# Smarttree_BMS_3_2.net
KiCad netlist of a schematic drawn in EAGLE
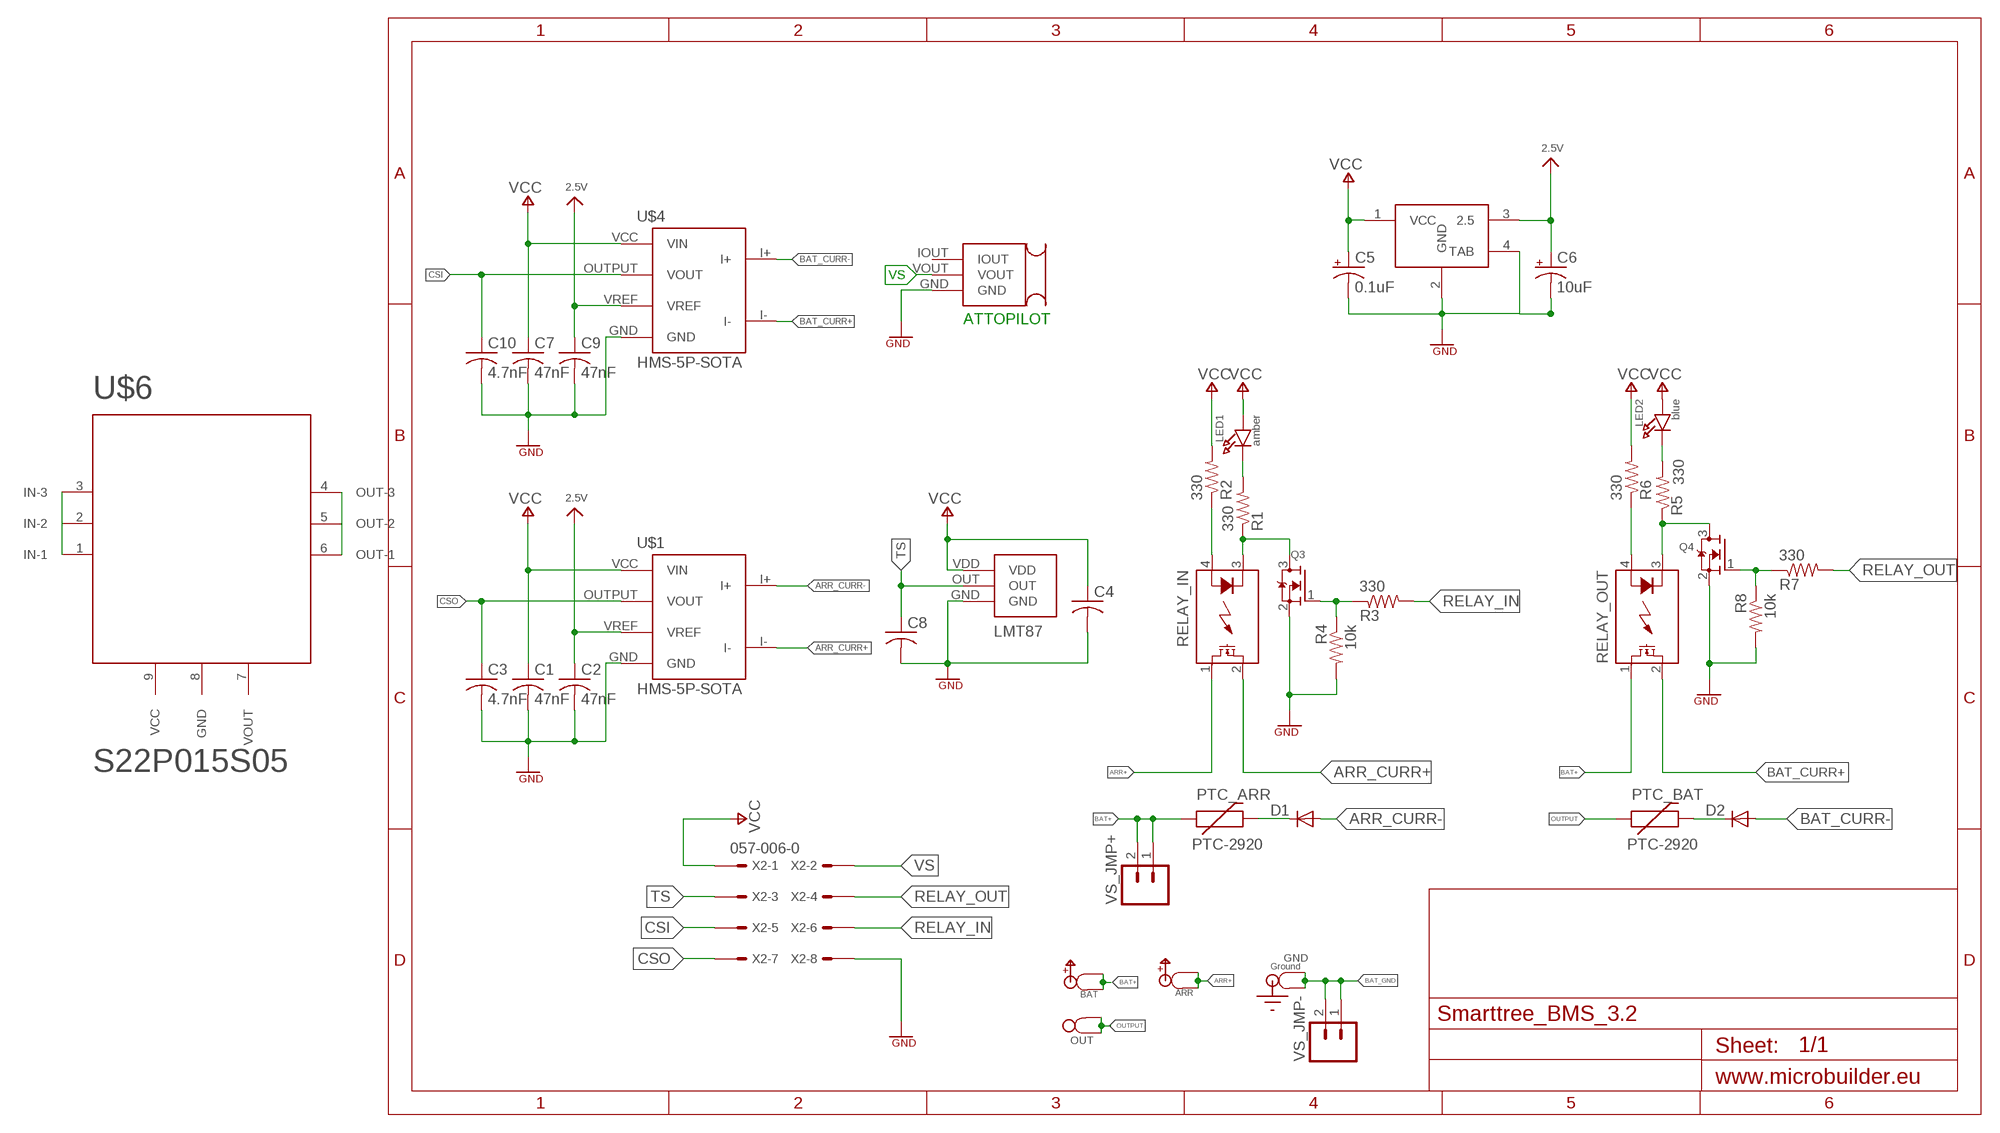
[diagram p0: schematic, sheet 1]

(export (version "E")
  (design (tool "Eeschema 10.0.6"))
  (components
    (comp (ref "ARR")
      (value "SPADE-POWER")
      (footprint "eagle-import:SPADE-POWER")
      (libsource (lib "eagle-import") (part "SPADE-POWER"))
    )
    (comp (ref "ATTOPILOT")
      (value "ATTOPILOT_VOLT")
      (footprint "eagle-import:TH_BKOT")
      (libsource (lib "eagle-import") (part "ATTOPILOT_VOLT"))
    )
    (comp (ref "BAT")
      (value "SPADE-POWER")
      (footprint "eagle-import:SPADE-POWER")
      (libsource (lib "eagle-import") (part "SPADE-POWER"))
    )
    (comp (ref "C1")
      (value "47nF")
      (footprint "eagle-import:C0805")
      (libsource (lib "eagle-import") (part "C-USC0805"))
    )
    (comp (ref "C2")
      (value "47nF")
      (footprint "eagle-import:C0805")
      (libsource (lib "eagle-import") (part "C-USC0805"))
    )
    (comp (ref "C3")
      (value "4.7nF")
      (footprint "eagle-import:C0805")
      (libsource (lib "eagle-import") (part "C-USC0805"))
    )
    (comp (ref "C4")
      (value "C-USC0805")
      (footprint "eagle-import:C0805")
      (libsource (lib "eagle-import") (part "C-USC0805"))
    )
    (comp (ref "C5")
      (value "0.1uF")
      (footprint "eagle-import:EIA3216")
      (libsource (lib "eagle-import") (part "10UF-TANT"))
    )
    (comp (ref "C6")
      (value "10uF")
      (footprint "eagle-import:EIA3216")
      (libsource (lib "eagle-import") (part "10UF-TANT"))
    )
    (comp (ref "C7")
      (value "47nF")
      (footprint "eagle-import:C0805")
      (libsource (lib "eagle-import") (part "C-USC0805"))
    )
    (comp (ref "C8")
      (value "C-USC0805")
      (footprint "eagle-import:C0805")
      (libsource (lib "eagle-import") (part "C-USC0805"))
    )
    (comp (ref "C9")
      (value "47nF")
      (footprint "eagle-import:C0805")
      (libsource (lib "eagle-import") (part "C-USC0805"))
    )
    (comp (ref "C10")
      (value "4.7nF")
      (footprint "eagle-import:C0805")
      (libsource (lib "eagle-import") (part "C-USC0805"))
    )
    (comp (ref "D1")
      (value "DIODE-SOD106-R")
      (footprint "eagle-import:SOD106-R")
      (libsource (lib "eagle-import") (part "DIODE-SOD106-R"))
    )
    (comp (ref "D2")
      (value "DIODE-SOD106-R")
      (footprint "eagle-import:SOD106-R")
      (libsource (lib "eagle-import") (part "DIODE-SOD106-R"))
    )
    (comp (ref "GND")
      (value "SPADE-GROUND")
      (footprint "eagle-import:SPADE-GROUND")
      (libsource (lib "eagle-import") (part "SPADE-GROUND"))
    )
    (comp (ref "LED1")
      (value "amber")
      (footprint "eagle-import:CHIPLED_0805")
      (libsource (lib "eagle-import") (part "LED0805"))
    )
    (comp (ref "LED2")
      (value "blue")
      (footprint "eagle-import:CHIPLED_0805")
      (libsource (lib "eagle-import") (part "LED0805"))
    )
    (comp (ref "LM1117")
      (value "LM2937_SOT223")
      (footprint "eagle-import:SOT223")
      (libsource (lib "eagle-import") (part "LM2937_SOT223"))
    )
    (comp (ref "LMT87")
      (value "LMT87_PAC")
      (footprint "eagle-import:LMT87_TO")
      (libsource (lib "eagle-import") (part "LMT87_PAC"))
    )
    (comp (ref "OUT")
      (value "SPADE-TERMINALPTH")
      (footprint "eagle-import:SPADE-TERMINAL")
      (libsource (lib "eagle-import") (part "SPADE-TERMINALPTH"))
    )
    (comp (ref "PTC_ARR")
      (value "PTC-2920")
      (footprint "eagle-import:PTC-2920")
      (libsource (lib "eagle-import") (part "PTC-2920"))
    )
    (comp (ref "PTC_BAT")
      (value "PTC-2920")
      (footprint "eagle-import:PTC-2920")
      (libsource (lib "eagle-import") (part "PTC-2920"))
    )
    (comp (ref "Q3")
      (value "MOSFET-NREFLOW")
      (footprint "eagle-import:SOT23")
      (libsource (lib "eagle-import") (part "MOSFET-NREFLOW"))
    )
    (comp (ref "Q4")
      (value "MOSFET-NREFLOW")
      (footprint "eagle-import:SOT23")
      (libsource (lib "eagle-import") (part "MOSFET-NREFLOW"))
    )
    (comp (ref "R1")
      (value "330")
      (footprint "eagle-import:R0805")
      (libsource (lib "eagle-import") (part "R-US_R0805"))
    )
    (comp (ref "R2")
      (value "330")
      (footprint "eagle-import:R0805")
      (libsource (lib "eagle-import") (part "R-US_R0805"))
    )
    (comp (ref "R3")
      (value "330")
      (footprint "eagle-import:R0805")
      (libsource (lib "eagle-import") (part "R-US_R0805"))
    )
    (comp (ref "R4")
      (value "10k")
      (footprint "eagle-import:R0805")
      (libsource (lib "eagle-import") (part "R-US_R0805"))
    )
    (comp (ref "R5")
      (value "330")
      (footprint "eagle-import:R0805")
      (libsource (lib "eagle-import") (part "R-US_R0805"))
    )
    (comp (ref "R6")
      (value "330")
      (footprint "eagle-import:R0805")
      (libsource (lib "eagle-import") (part "R-US_R0805"))
    )
    (comp (ref "R7")
      (value "330")
      (footprint "eagle-import:R0805")
      (libsource (lib "eagle-import") (part "R-US_R0805"))
    )
    (comp (ref "R8")
      (value "10k")
      (footprint "eagle-import:R0805")
      (libsource (lib "eagle-import") (part "R-US_R0805"))
    )
    (comp (ref "RELAY_IN")
      (value "CPC1708J")
      (footprint "eagle-import:I4-PAC")
      (libsource (lib "eagle-import") (part "CPC1708J"))
    )
    (comp (ref "RELAY_OUT")
      (value "CPC1708J")
      (footprint "eagle-import:I4-PAC")
      (libsource (lib "eagle-import") (part "CPC1708J"))
    )
    (comp (ref "U$1")
      (value "HMS-5P-SOTA")
      (footprint "eagle-import:SMD_CURR_SENSE")
      (libsource (lib "eagle-import") (part "HMS-5P-SOTA"))
    )
    (comp (ref "U$4")
      (value "HMS-5P-SOTA")
      (footprint "eagle-import:SMD_CURR_SENSE")
      (libsource (lib "eagle-import") (part "HMS-5P-SOTA"))
    )
    (comp (ref "U$6")
      (value "S22P015S05")
      (footprint "eagle-import:S22P015S05")
      (libsource (lib "eagle-import") (part "S22P015S05"))
    )
    (comp (ref "VS_JMP+")
      (value "M02")
      (footprint "eagle-import:1X02_LONGPADS")
      (libsource (lib "eagle-import") (part "M02"))
    )
    (comp (ref "VS_JMP-")
      (value "M02")
      (footprint "eagle-import:1X02_LONGPADS")
      (libsource (lib "eagle-import") (part "M02"))
    )
    (comp (ref "X2")
      (value "057-006-0")
      (footprint "eagle-import:057-006-0")
      (libsource (lib "eagle-import") (part "057-006-0"))
    )
  )
  (nets
    (net (code "1") (name "2.5V") (class "Default")
      (node (ref "C2") (pin "1") (pinfunction "1_1") (pintype "passive"))
      (node (ref "C6") (pin "A") (pinfunction "+_A") (pintype "passive"))
      (node (ref "C9") (pin "1") (pinfunction "1_1") (pintype "passive"))
      (node (ref "LM1117") (pin "3") (pinfunction "2.5_3") (pintype "bidirectional"))
      (node (ref "U$1") (pin "VREF") (pinfunction "VREF_VREF") (pintype "bidirectional"))
      (node (ref "U$4") (pin "VREF") (pinfunction "VREF_VREF") (pintype "bidirectional"))
    )
    (net (code "2") (name "5V") (class "Default")
      (node (ref "C1") (pin "1") (pinfunction "1_1") (pintype "passive"))
      (node (ref "C4") (pin "1") (pinfunction "1_1") (pintype "passive"))
      (node (ref "C5") (pin "A") (pinfunction "+_A") (pintype "passive"))
      (node (ref "C7") (pin "1") (pinfunction "1_1") (pintype "passive"))
      (node (ref "LED1") (pin "A") (pinfunction "A_A") (pintype "passive"))
      (node (ref "LED2") (pin "A") (pinfunction "A_A") (pintype "passive"))
      (node (ref "LM1117") (pin "1") (pinfunction "VCC_1") (pintype "bidirectional"))
      (node (ref "LMT87") (pin "VDD") (pinfunction "VDD_VDD") (pintype "bidirectional"))
      (node (ref "R2") (pin "2") (pinfunction "2_2") (pintype "passive"))
      (node (ref "R6") (pin "2") (pinfunction "2_2") (pintype "passive"))
      (node (ref "U$1") (pin "VCC") (pinfunction "VIN_VCC") (pintype "bidirectional"))
      (node (ref "U$4") (pin "VCC") (pinfunction "VIN_VCC") (pintype "bidirectional"))
      (node (ref "X2") (pin "1") (pinfunction "S_1") (pintype "passive"))
    )
    (net (code "3") (name "ARR+") (class "Default")
      (node (ref "ARR") (pin "P$1") (pinfunction "P$1_P$1") (pintype "bidirectional"))
      (node (ref "ARR") (pin "P$2") (pinfunction "P$2_P$2") (pintype "bidirectional"))
      (node (ref "RELAY_IN") (pin "1") (pinfunction "DS1_1") (pintype "passive"))
    )
    (net (code "4") (name "ARR_CURR+") (class "Default")
      (node (ref "RELAY_IN") (pin "2") (pinfunction "DS2_2") (pintype "passive"))
      (node (ref "U$1") (pin "I-") (pinfunction "I-_I-") (pintype "bidirectional"))
    )
    (net (code "5") (name "ARR_CURR-") (class "Default")
      (node (ref "D1") (pin "A") (pinfunction "A_A") (pintype "passive"))
      (node (ref "U$1") (pin "I+") (pinfunction "I+_I+") (pintype "bidirectional"))
    )
    (net (code "6") (name "BAT+") (class "Default")
      (node (ref "BAT") (pin "P$1") (pinfunction "P$1_P$1") (pintype "bidirectional"))
      (node (ref "BAT") (pin "P$2") (pinfunction "P$2_P$2") (pintype "bidirectional"))
      (node (ref "PTC_ARR") (pin "1") (pinfunction "1_1") (pintype "bidirectional"))
      (node (ref "RELAY_OUT") (pin "1") (pinfunction "DS1_1") (pintype "passive"))
      (node (ref "VS_JMP+") (pin "1") (pinfunction "1_1") (pintype "passive"))
      (node (ref "VS_JMP+") (pin "2") (pinfunction "2_2") (pintype "passive"))
    )
    (net (code "7") (name "BAT_CURR+") (class "Default")
      (node (ref "RELAY_OUT") (pin "2") (pinfunction "DS2_2") (pintype "passive"))
      (node (ref "U$4") (pin "I-") (pinfunction "I-_I-") (pintype "bidirectional"))
    )
    (net (code "8") (name "BAT_CURR-") (class "Default")
      (node (ref "D2") (pin "A") (pinfunction "A_A") (pintype "passive"))
      (node (ref "U$4") (pin "I+") (pinfunction "I+_I+") (pintype "bidirectional"))
    )
    (net (code "9") (name "BAT_GND") (class "Default")
      (node (ref "GND") (pin "P$1") (pinfunction "P$1_P$1") (pintype "bidirectional"))
      (node (ref "GND") (pin "P$2") (pinfunction "P$2_P$2") (pintype "bidirectional"))
      (node (ref "VS_JMP-") (pin "1") (pinfunction "1_1") (pintype "passive"))
      (node (ref "VS_JMP-") (pin "2") (pinfunction "2_2") (pintype "passive"))
    )
    (net (code "10") (name "CSI") (class "Default")
      (node (ref "C10") (pin "1") (pinfunction "1_1") (pintype "passive"))
      (node (ref "U$4") (pin "OUTPUT") (pinfunction "VOUT_OUTPUT") (pintype "bidirectional"))
      (node (ref "X2") (pin "5") (pinfunction "S_5") (pintype "passive"))
    )
    (net (code "11") (name "CSO") (class "Default")
      (node (ref "C3") (pin "1") (pinfunction "1_1") (pintype "passive"))
      (node (ref "U$1") (pin "OUTPUT") (pinfunction "VOUT_OUTPUT") (pintype "bidirectional"))
      (node (ref "X2") (pin "8") (pinfunction "S_8") (pintype "passive"))
    )
    (net (code "12") (name "GND") (class "Default")
      (node (ref "ATTOPILOT") (pin "GND") (pinfunction "GND_GND") (pintype "bidirectional"))
      (node (ref "C1") (pin "2") (pinfunction "2_2") (pintype "passive"))
      (node (ref "C10") (pin "2") (pinfunction "2_2") (pintype "passive"))
      (node (ref "C2") (pin "2") (pinfunction "2_2") (pintype "passive"))
      (node (ref "C3") (pin "2") (pinfunction "2_2") (pintype "passive"))
      (node (ref "C4") (pin "2") (pinfunction "2_2") (pintype "passive"))
      (node (ref "C5") (pin "C") (pinfunction "-_C") (pintype "passive"))
      (node (ref "C6") (pin "C") (pinfunction "-_C") (pintype "passive"))
      (node (ref "C7") (pin "2") (pinfunction "2_2") (pintype "passive"))
      (node (ref "C8") (pin "2") (pinfunction "2_2") (pintype "passive"))
      (node (ref "C9") (pin "2") (pinfunction "2_2") (pintype "passive"))
      (node (ref "LM1117") (pin "2") (pinfunction "GND_2") (pintype "bidirectional"))
      (node (ref "LM1117") (pin "4") (pinfunction "TAB_4") (pintype "bidirectional"))
      (node (ref "LMT87") (pin "GND") (pinfunction "GND_GND") (pintype "bidirectional"))
      (node (ref "Q3") (pin "2") (pinfunction "S_2") (pintype "bidirectional"))
      (node (ref "Q4") (pin "2") (pinfunction "S_2") (pintype "bidirectional"))
      (node (ref "R4") (pin "2") (pinfunction "2_2") (pintype "passive"))
      (node (ref "R8") (pin "2") (pinfunction "2_2") (pintype "passive"))
      (node (ref "U$1") (pin "GND") (pinfunction "GND_GND") (pintype "bidirectional"))
      (node (ref "U$4") (pin "GND") (pinfunction "GND_GND") (pintype "bidirectional"))
      (node (ref "X2") (pin "7") (pinfunction "S_7") (pintype "passive"))
    )
    (net (code "13") (name "Net-(D1-PadC)") (class "Default")
      (node (ref "D1") (pin "C") (pinfunction "C_C") (pintype "passive"))
      (node (ref "PTC_ARR") (pin "2") (pinfunction "2_2") (pintype "bidirectional"))
    )
    (net (code "14") (name "Net-(D2-PadC)") (class "Default")
      (node (ref "D2") (pin "C") (pinfunction "C_C") (pintype "passive"))
      (node (ref "PTC_BAT") (pin "2") (pinfunction "2_2") (pintype "bidirectional"))
    )
    (net (code "15") (name "Net-(LED1-PadC)") (class "Default")
      (node (ref "LED1") (pin "C") (pinfunction "C_C") (pintype "passive"))
      (node (ref "R1") (pin "2") (pinfunction "2_2") (pintype "passive"))
    )
    (net (code "16") (name "Net-(LED2-PadC)") (class "Default")
      (node (ref "LED2") (pin "C") (pinfunction "C_C") (pintype "passive"))
      (node (ref "R5") (pin "2") (pinfunction "2_2") (pintype "passive"))
    )
    (net (code "17") (name "Net-(Q3-D)") (class "Default")
      (node (ref "Q3") (pin "3") (pinfunction "D_3") (pintype "bidirectional"))
      (node (ref "R1") (pin "1") (pinfunction "1_1") (pintype "passive"))
      (node (ref "RELAY_IN") (pin "3") (pinfunction "K_3") (pintype "passive"))
    )
    (net (code "18") (name "Net-(Q3-G)") (class "Default")
      (node (ref "Q3") (pin "1") (pinfunction "G_1") (pintype "bidirectional"))
      (node (ref "R3") (pin "1") (pinfunction "1_1") (pintype "passive"))
      (node (ref "R4") (pin "1") (pinfunction "1_1") (pintype "passive"))
    )
    (net (code "19") (name "Net-(Q4-D)") (class "Default")
      (node (ref "Q4") (pin "3") (pinfunction "D_3") (pintype "bidirectional"))
      (node (ref "R5") (pin "1") (pinfunction "1_1") (pintype "passive"))
      (node (ref "RELAY_OUT") (pin "3") (pinfunction "K_3") (pintype "passive"))
    )
    (net (code "20") (name "Net-(Q4-G)") (class "Default")
      (node (ref "Q4") (pin "1") (pinfunction "G_1") (pintype "bidirectional"))
      (node (ref "R7") (pin "1") (pinfunction "1_1") (pintype "passive"))
      (node (ref "R8") (pin "1") (pinfunction "1_1") (pintype "passive"))
    )
    (net (code "21") (name "Net-(RELAY_IN-A)") (class "Default")
      (node (ref "R2") (pin "1") (pinfunction "1_1") (pintype "passive"))
      (node (ref "RELAY_IN") (pin "4") (pinfunction "A_4") (pintype "passive"))
    )
    (net (code "22") (name "Net-(RELAY_OUT-A)") (class "Default")
      (node (ref "R6") (pin "1") (pinfunction "1_1") (pintype "passive"))
      (node (ref "RELAY_OUT") (pin "4") (pinfunction "A_4") (pintype "passive"))
    )
    (net (code "23") (name "OUTPUT") (class "Default")
      (node (ref "OUT") (pin "P$1") (pinfunction "P$1_P$1") (pintype "bidirectional"))
      (node (ref "OUT") (pin "P$2") (pinfunction "P$2_P$2") (pintype "bidirectional"))
      (node (ref "PTC_BAT") (pin "1") (pinfunction "1_1") (pintype "bidirectional"))
    )
    (net (code "24") (name "RELAY_IN") (class "Default")
      (node (ref "R3") (pin "2") (pinfunction "2_2") (pintype "passive"))
      (node (ref "X2") (pin "6") (pinfunction "S_6") (pintype "passive"))
    )
    (net (code "25") (name "RELAY_OUT") (class "Default")
      (node (ref "R7") (pin "2") (pinfunction "2_2") (pintype "passive"))
      (node (ref "X2") (pin "4") (pinfunction "S_4") (pintype "passive"))
    )
    (net (code "26") (name "TS") (class "Default")
      (node (ref "C8") (pin "1") (pinfunction "1_1") (pintype "passive"))
      (node (ref "LMT87") (pin "OUT") (pinfunction "OUT_OUT") (pintype "bidirectional"))
      (node (ref "X2") (pin "3") (pinfunction "S_3") (pintype "passive"))
    )
    (net (code "27") (name "VS") (class "Default")
      (node (ref "ATTOPILOT") (pin "VOUT") (pinfunction "VOUT_VOUT") (pintype "bidirectional"))
      (node (ref "X2") (pin "2") (pinfunction "S_2") (pintype "passive"))
    )
    (net (code "28") (name "unconnected-(ATTOPILOT-PadIOUT)") (class "Default")
      (node (ref "ATTOPILOT") (pin "IOUT") (pinfunction "IOUT_IOUT") (pintype "bidirectional"))
    )
    (net (code "29") (name "unconnected-(U$6-GND-Pad8)") (class "Default")
      (node (ref "U$6") (pin "8") (pinfunction "GND_8") (pintype "bidirectional"))
    )
    (net (code "30") (name "unconnected-(U$6-IN-1-Pad1)") (class "Default")
      (node (ref "U$6") (pin "1") (pinfunction "IN-1_1") (pintype "bidirectional"))
    )
    (net (code "31") (name "unconnected-(U$6-IN-2-Pad2)") (class "Default")
      (node (ref "U$6") (pin "2") (pinfunction "IN-2_2") (pintype "bidirectional"))
    )
    (net (code "32") (name "unconnected-(U$6-IN-3-Pad3)") (class "Default")
      (node (ref "U$6") (pin "3") (pinfunction "IN-3_3") (pintype "bidirectional"))
    )
    (net (code "33") (name "unconnected-(U$6-OUT-1-Pad6)") (class "Default")
      (node (ref "U$6") (pin "6") (pinfunction "OUT-1_6") (pintype "bidirectional"))
    )
    (net (code "34") (name "unconnected-(U$6-OUT-2-Pad5)") (class "Default")
      (node (ref "U$6") (pin "5") (pinfunction "OUT-2_5") (pintype "bidirectional"))
    )
    (net (code "35") (name "unconnected-(U$6-OUT-3-Pad4)") (class "Default")
      (node (ref "U$6") (pin "4") (pinfunction "OUT-3_4") (pintype "bidirectional"))
    )
    (net (code "36") (name "unconnected-(U$6-VCC-Pad9)") (class "Default")
      (node (ref "U$6") (pin "9") (pinfunction "VCC_9") (pintype "bidirectional"))
    )
    (net (code "37") (name "unconnected-(U$6-VOUT-Pad7)") (class "Default")
      (node (ref "U$6") (pin "7") (pinfunction "VOUT_7") (pintype "bidirectional"))
    )
  )
)
